# receiver_ra02.net
KiCad netlist of a schematic drawn in EAGLE
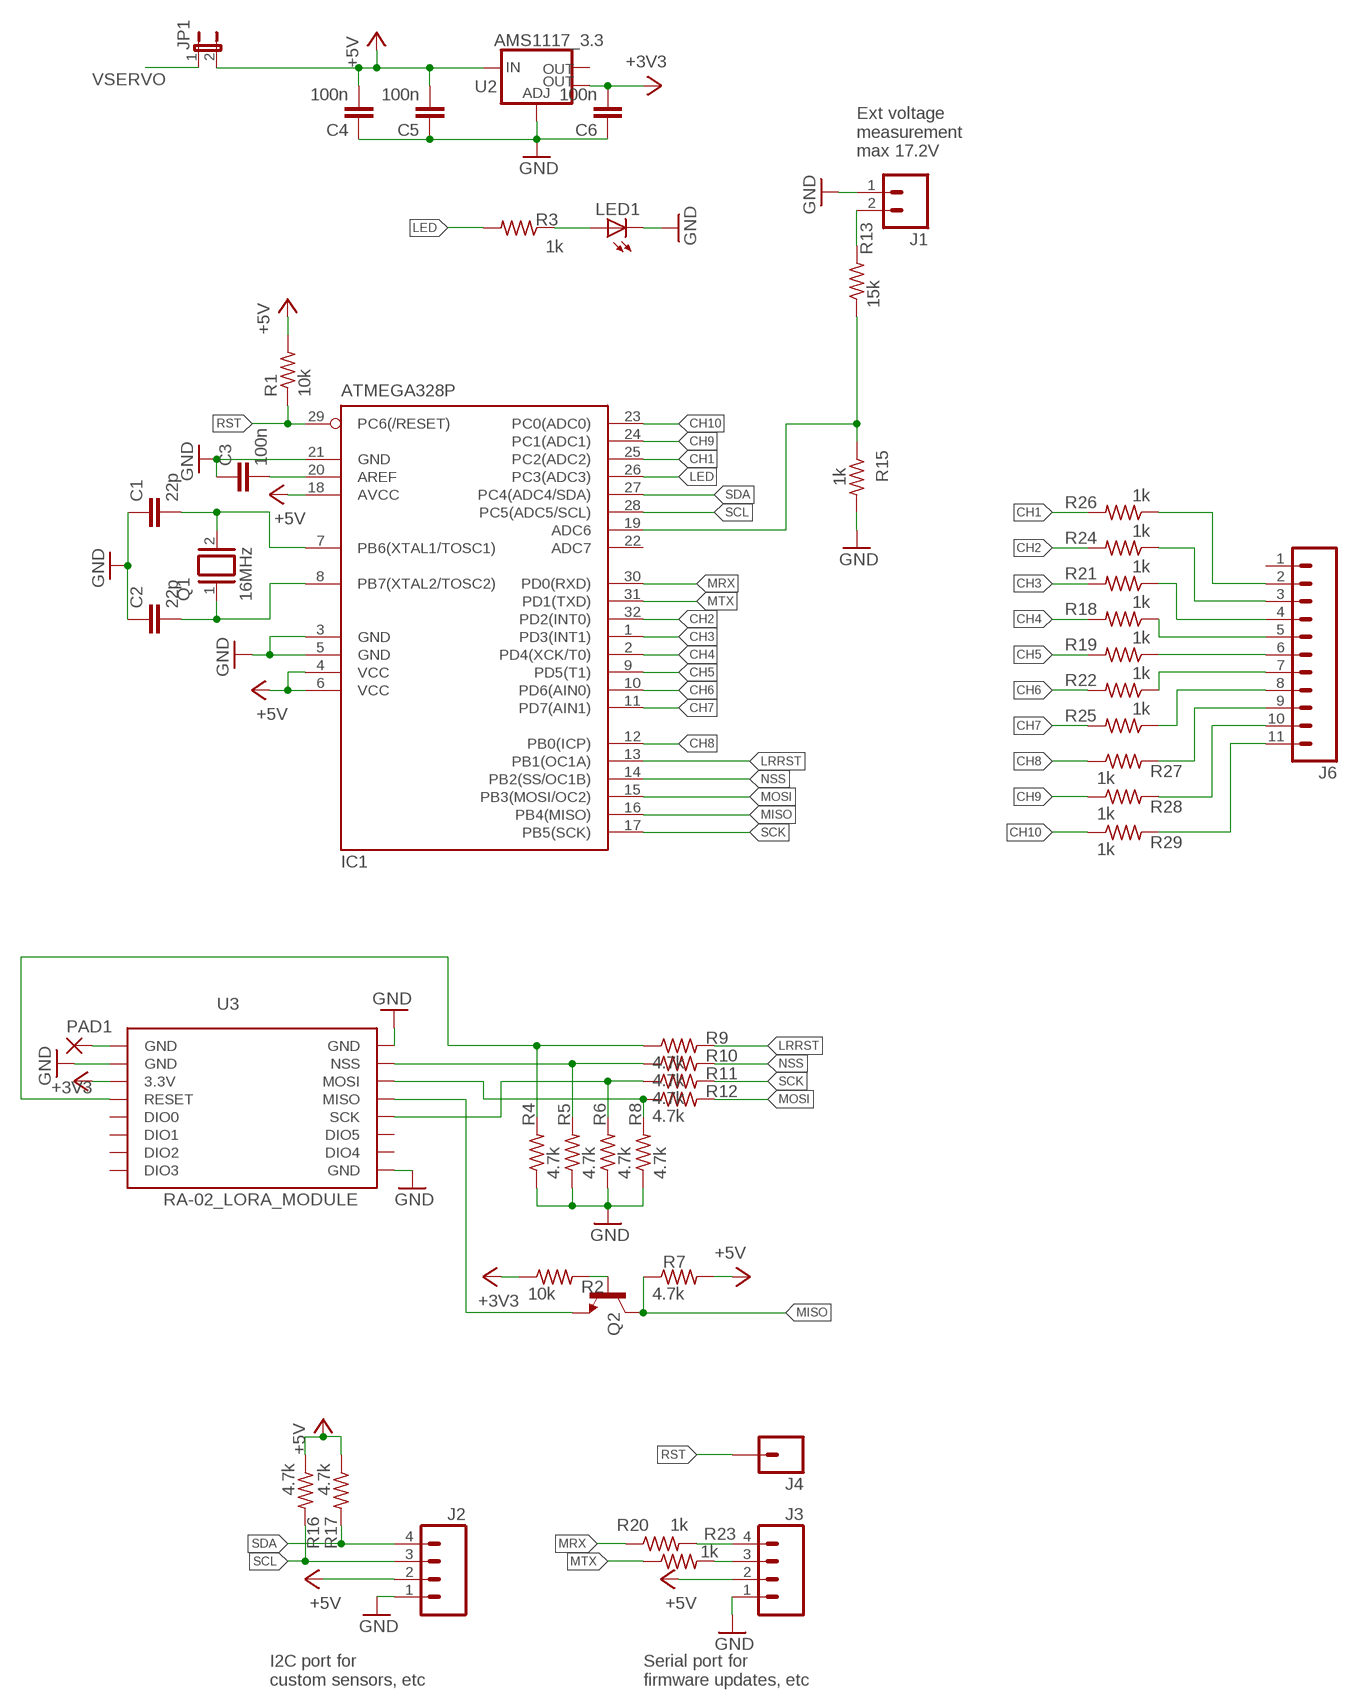
[diagram p0: schematic, sheet 1]

(export (version "E")
  (design (tool "Eeschema 10.0.6"))
  (components
    (comp (ref "C1")
      (value "22p")
      (footprint "eagle-import:C0805K")
      (libsource (lib "eagle-import") (part "C-EUC0805K"))
    )
    (comp (ref "C2")
      (value "22p")
      (footprint "eagle-import:C0805K")
      (libsource (lib "eagle-import") (part "C-EUC0805K"))
    )
    (comp (ref "C3")
      (value "100n")
      (footprint "eagle-import:C0805K")
      (libsource (lib "eagle-import") (part "C-EUC0805K"))
    )
    (comp (ref "C4")
      (value "100n")
      (footprint "eagle-import:C0805K")
      (libsource (lib "eagle-import") (part "C-EUC0805K"))
    )
    (comp (ref "C5")
      (value "100n")
      (footprint "eagle-import:C0805K")
      (libsource (lib "eagle-import") (part "C-EUC0805K"))
    )
    (comp (ref "C6")
      (value "100n")
      (footprint "eagle-import:C0805K")
      (libsource (lib "eagle-import") (part "C-EUC0805K"))
    )
    (comp (ref "IC1")
      (value "ATMEGA328P")
      (footprint "eagle-import:TQFP32-08")
      (fields (field (name "MPN") "ATMEGA8-16AU"))
      (libsource (lib "eagle-import") (part "MEGA8-AI"))
    )
    (comp (ref "J1")
      (value "M02PTH")
      (footprint "eagle-import:1X02")
      (libsource (lib "eagle-import") (part "M02PTH"))
    )
    (comp (ref "J2")
      (value "M04PTH")
      (footprint "eagle-import:1X04")
      (libsource (lib "eagle-import") (part "M04PTH"))
    )
    (comp (ref "J3")
      (value "M04PTH")
      (footprint "eagle-import:1X04")
      (libsource (lib "eagle-import") (part "M04PTH"))
    )
    (comp (ref "J4")
      (value "M01PTH")
      (footprint "eagle-import:1X01")
      (libsource (lib "eagle-import") (part "M01PTH"))
    )
    (comp (ref "J6")
      (value "M11PTH")
      (footprint "eagle-import:1X11")
      (libsource (lib "eagle-import") (part "M11PTH"))
    )
    (comp (ref "JP1")
      (value "JP1E")
      (footprint "eagle-import:JP1")
      (libsource (lib "eagle-import") (part "JP1E"))
    )
    (comp (ref "LED1")
      (value "LEDCHIPLED_1206")
      (footprint "eagle-import:CHIPLED_1206")
      (libsource (lib "eagle-import") (part "LEDCHIPLED_1206"))
    )
    (comp (ref "PAD1")
      (value "2,15/1,0")
      (footprint "eagle-import:2,15_1,0")
      (libsource (lib "eagle-import") (part "2,15/1,0"))
    )
    (comp (ref "Q1")
      (value "16MHz")
      (footprint "eagle-import:QS")
      (libsource (lib "eagle-import") (part "XTAL/S"))
    )
    (comp (ref "Q2")
      (value "BC817-16SMD")
      (footprint "eagle-import:SOT23-BEC")
      (libsource (lib "eagle-import") (part "BC817SMD-16"))
    )
    (comp (ref "R1")
      (value "10k")
      (footprint "eagle-import:R0805")
      (libsource (lib "eagle-import") (part "R-US_R0805"))
    )
    (comp (ref "R2")
      (value "10k")
      (footprint "eagle-import:R0805")
      (libsource (lib "eagle-import") (part "R-US_R0805"))
    )
    (comp (ref "R3")
      (value "1k")
      (footprint "eagle-import:R0805")
      (libsource (lib "eagle-import") (part "R-US_R0805"))
    )
    (comp (ref "R4")
      (value "4.7k")
      (footprint "eagle-import:R0805")
      (libsource (lib "eagle-import") (part "R-US_R0805"))
    )
    (comp (ref "R5")
      (value "4.7k")
      (footprint "eagle-import:R0805")
      (libsource (lib "eagle-import") (part "R-US_R0805"))
    )
    (comp (ref "R6")
      (value "4.7k")
      (footprint "eagle-import:R0805")
      (libsource (lib "eagle-import") (part "R-US_R0805"))
    )
    (comp (ref "R7")
      (value "4.7k")
      (footprint "eagle-import:R0805")
      (libsource (lib "eagle-import") (part "R-US_R0805"))
    )
    (comp (ref "R8")
      (value "4.7k")
      (footprint "eagle-import:R0805")
      (libsource (lib "eagle-import") (part "R-US_R0805"))
    )
    (comp (ref "R9")
      (value "4.7k")
      (footprint "eagle-import:R0805")
      (libsource (lib "eagle-import") (part "R-US_R0805"))
    )
    (comp (ref "R10")
      (value "4.7k")
      (footprint "eagle-import:R0805")
      (libsource (lib "eagle-import") (part "R-US_R0805"))
    )
    (comp (ref "R11")
      (value "4.7k")
      (footprint "eagle-import:R0805")
      (libsource (lib "eagle-import") (part "R-US_R0805"))
    )
    (comp (ref "R12")
      (value "4.7k")
      (footprint "eagle-import:R0805")
      (libsource (lib "eagle-import") (part "R-US_R0805"))
    )
    (comp (ref "R13")
      (value "15k")
      (footprint "eagle-import:R0805")
      (libsource (lib "eagle-import") (part "R-US_R0805"))
    )
    (comp (ref "R15")
      (value "1k")
      (footprint "eagle-import:R0805")
      (libsource (lib "eagle-import") (part "R-US_R0805"))
    )
    (comp (ref "R16")
      (value "4.7k")
      (footprint "eagle-import:R0805")
      (libsource (lib "eagle-import") (part "R-US_R0805"))
    )
    (comp (ref "R17")
      (value "4.7k")
      (footprint "eagle-import:R0805")
      (libsource (lib "eagle-import") (part "R-US_R0805"))
    )
    (comp (ref "R18")
      (value "1k")
      (footprint "eagle-import:R0805")
      (libsource (lib "eagle-import") (part "R-US_R0805"))
    )
    (comp (ref "R19")
      (value "1k")
      (footprint "eagle-import:R0805")
      (libsource (lib "eagle-import") (part "R-US_R0805"))
    )
    (comp (ref "R20")
      (value "1k")
      (footprint "eagle-import:R0805")
      (libsource (lib "eagle-import") (part "R-US_R0805"))
    )
    (comp (ref "R21")
      (value "1k")
      (footprint "eagle-import:R0805")
      (libsource (lib "eagle-import") (part "R-US_R0805"))
    )
    (comp (ref "R22")
      (value "1k")
      (footprint "eagle-import:R0805")
      (libsource (lib "eagle-import") (part "R-US_R0805"))
    )
    (comp (ref "R23")
      (value "1k")
      (footprint "eagle-import:R0805")
      (libsource (lib "eagle-import") (part "R-US_R0805"))
    )
    (comp (ref "R24")
      (value "1k")
      (footprint "eagle-import:R0805")
      (libsource (lib "eagle-import") (part "R-US_R0805"))
    )
    (comp (ref "R25")
      (value "1k")
      (footprint "eagle-import:R0805")
      (libsource (lib "eagle-import") (part "R-US_R0805"))
    )
    (comp (ref "R26")
      (value "1k")
      (footprint "eagle-import:R0805")
      (libsource (lib "eagle-import") (part "R-US_R0805"))
    )
    (comp (ref "R27")
      (value "1k")
      (footprint "eagle-import:R0805")
      (libsource (lib "eagle-import") (part "R-US_R0805"))
    )
    (comp (ref "R28")
      (value "1k")
      (footprint "eagle-import:R0805")
      (libsource (lib "eagle-import") (part "R-US_R0805"))
    )
    (comp (ref "R29")
      (value "1k")
      (footprint "eagle-import:R0805")
      (libsource (lib "eagle-import") (part "R-US_R0805"))
    )
    (comp (ref "U2")
      (value "AMS1117_3.3")
      (footprint "eagle-import:SOT223")
      (libsource (lib "eagle-import") (part "V_REG_LM1117SOT223"))
    )
    (comp (ref "U3")
      (value "RA-02_LORA_MODULE")
      (footprint "eagle-import:RA-02")
      (libsource (lib "eagle-import") (part "RA-02_LORA_MODULE"))
    )
  )
  (nets
    (net (code "1") (name "+3V3") (class "Default")
      (node (ref "C6") (pin "2") (pinfunction "2_2") (pintype "passive"))
      (node (ref "R2") (pin "1") (pinfunction "1_1") (pintype "passive"))
      (node (ref "U2") (pin "4") (pinfunction "OUT_4") (pintype "output"))
      (node (ref "U3") (pin "3.3V") (pinfunction "3.3V_3.3V") (pintype "power_in"))
    )
    (net (code "2") (name "+5V") (class "Default")
      (node (ref "C4") (pin "2") (pinfunction "2_2") (pintype "passive"))
      (node (ref "C5") (pin "2") (pinfunction "2_2") (pintype "passive"))
      (node (ref "IC1") (pin "18") (pinfunction "AVCC_18") (pintype "power_in"))
      (node (ref "IC1") (pin "4") (pinfunction "VCC_4") (pintype "power_in"))
      (node (ref "IC1") (pin "6") (pinfunction "VCC_6") (pintype "power_in"))
      (node (ref "J2") (pin "2") (pinfunction "2_2") (pintype "passive"))
      (node (ref "J3") (pin "2") (pinfunction "2_2") (pintype "passive"))
      (node (ref "JP1") (pin "2") (pinfunction "2_2") (pintype "passive"))
      (node (ref "R1") (pin "2") (pinfunction "2_2") (pintype "passive"))
      (node (ref "R16") (pin "1") (pinfunction "1_1") (pintype "passive"))
      (node (ref "R17") (pin "1") (pinfunction "1_1") (pintype "passive"))
      (node (ref "R7") (pin "2") (pinfunction "2_2") (pintype "passive"))
      (node (ref "U2") (pin "3") (pinfunction "IN_3") (pintype "input"))
    )
    (net (code "3") (name "/VSERVO") (class "Default")
      (node (ref "JP1") (pin "1") (pinfunction "1_1") (pintype "passive"))
    )
    (net (code "4") (name "CH1") (class "Default")
      (node (ref "IC1") (pin "25") (pinfunction "PC2(ADC2)_25") (pintype "bidirectional"))
      (node (ref "R26") (pin "2") (pinfunction "2_2") (pintype "passive"))
    )
    (net (code "5") (name "CH2") (class "Default")
      (node (ref "IC1") (pin "32") (pinfunction "PD2(INT0)_32") (pintype "bidirectional"))
      (node (ref "R24") (pin "2") (pinfunction "2_2") (pintype "passive"))
    )
    (net (code "6") (name "CH3") (class "Default")
      (node (ref "IC1") (pin "1") (pinfunction "PD3(INT1)_1") (pintype "bidirectional"))
      (node (ref "R21") (pin "2") (pinfunction "2_2") (pintype "passive"))
    )
    (net (code "7") (name "CH4") (class "Default")
      (node (ref "IC1") (pin "2") (pinfunction "PD4(XCK/T0)_2") (pintype "bidirectional"))
      (node (ref "R18") (pin "2") (pinfunction "2_2") (pintype "passive"))
    )
    (net (code "8") (name "CH5") (class "Default")
      (node (ref "IC1") (pin "9") (pinfunction "PD5(T1)_9") (pintype "bidirectional"))
      (node (ref "R19") (pin "2") (pinfunction "2_2") (pintype "passive"))
    )
    (net (code "9") (name "CH6") (class "Default")
      (node (ref "IC1") (pin "10") (pinfunction "PD6(AIN0)_10") (pintype "bidirectional"))
      (node (ref "R22") (pin "2") (pinfunction "2_2") (pintype "passive"))
    )
    (net (code "10") (name "CH7") (class "Default")
      (node (ref "IC1") (pin "11") (pinfunction "PD7(AIN1)_11") (pintype "bidirectional"))
      (node (ref "R25") (pin "2") (pinfunction "2_2") (pintype "passive"))
    )
    (net (code "11") (name "CH8") (class "Default")
      (node (ref "IC1") (pin "12") (pinfunction "PB0(ICP)_12") (pintype "bidirectional"))
      (node (ref "R27") (pin "1") (pinfunction "1_1") (pintype "passive"))
    )
    (net (code "12") (name "CH9") (class "Default")
      (node (ref "IC1") (pin "24") (pinfunction "PC1(ADC1)_24") (pintype "bidirectional"))
      (node (ref "R28") (pin "1") (pinfunction "1_1") (pintype "passive"))
    )
    (net (code "13") (name "CH10") (class "Default")
      (node (ref "IC1") (pin "23") (pinfunction "PC0(ADC0)_23") (pintype "bidirectional"))
      (node (ref "R29") (pin "1") (pinfunction "1_1") (pintype "passive"))
    )
    (net (code "14") (name "GND") (class "Default")
      (node (ref "C1") (pin "1") (pinfunction "1_1") (pintype "passive"))
      (node (ref "C2") (pin "1") (pinfunction "1_1") (pintype "passive"))
      (node (ref "C3") (pin "1") (pinfunction "1_1") (pintype "passive"))
      (node (ref "C4") (pin "1") (pinfunction "1_1") (pintype "passive"))
      (node (ref "C5") (pin "1") (pinfunction "1_1") (pintype "passive"))
      (node (ref "C6") (pin "1") (pinfunction "1_1") (pintype "passive"))
      (node (ref "IC1") (pin "21") (pinfunction "GND_21") (pintype "power_in"))
      (node (ref "IC1") (pin "3") (pinfunction "GND_3") (pintype "power_in"))
      (node (ref "IC1") (pin "5") (pinfunction "GND_5") (pintype "power_in"))
      (node (ref "J1") (pin "1") (pinfunction "1_1") (pintype "passive"))
      (node (ref "J2") (pin "1") (pinfunction "1_1") (pintype "passive"))
      (node (ref "J3") (pin "1") (pinfunction "1_1") (pintype "passive"))
      (node (ref "LED1") (pin "C") (pinfunction "C_C") (pintype "passive"))
      (node (ref "R15") (pin "2") (pinfunction "2_2") (pintype "passive"))
      (node (ref "R4") (pin "1") (pinfunction "1_1") (pintype "passive"))
      (node (ref "R5") (pin "1") (pinfunction "1_1") (pintype "passive"))
      (node (ref "R6") (pin "1") (pinfunction "1_1") (pintype "passive"))
      (node (ref "R8") (pin "1") (pinfunction "1_1") (pintype "passive"))
      (node (ref "U2") (pin "1") (pinfunction "ADJ_1") (pintype "input"))
      (node (ref "U3") (pin "GND@2") (pinfunction "GND_GND@2") (pintype "power_in"))
      (node (ref "U3") (pin "GND@3") (pinfunction "GND_GND@3") (pintype "power_in"))
      (node (ref "U3") (pin "GND@4") (pinfunction "GND_GND@4") (pintype "power_in"))
    )
    (net (code "15") (name "LED") (class "Default")
      (node (ref "IC1") (pin "26") (pinfunction "PC3(ADC3)_26") (pintype "bidirectional"))
      (node (ref "R3") (pin "2") (pinfunction "2_2") (pintype "passive"))
    )
    (net (code "16") (name "LRRST") (class "Default")
      (node (ref "IC1") (pin "13") (pinfunction "PB1(OC1A)_13") (pintype "bidirectional"))
      (node (ref "R9") (pin "2") (pinfunction "2_2") (pintype "passive"))
    )
    (net (code "17") (name "MISO") (class "Default")
      (node (ref "IC1") (pin "16") (pinfunction "PB4(MISO)_16") (pintype "bidirectional"))
      (node (ref "Q2") (pin "C") (pinfunction "C_C") (pintype "passive"))
      (node (ref "R7") (pin "1") (pinfunction "1_1") (pintype "passive"))
    )
    (net (code "18") (name "MOSI") (class "Default")
      (node (ref "IC1") (pin "15") (pinfunction "PB3(MOSI/OC2)_15") (pintype "bidirectional"))
      (node (ref "R12") (pin "2") (pinfunction "2_2") (pintype "passive"))
    )
    (net (code "19") (name "MRX") (class "Default")
      (node (ref "IC1") (pin "30") (pinfunction "PD0(RXD)_30") (pintype "bidirectional"))
      (node (ref "R20") (pin "1") (pinfunction "1_1") (pintype "passive"))
    )
    (net (code "20") (name "MTX") (class "Default")
      (node (ref "IC1") (pin "31") (pinfunction "PD1(TXD)_31") (pintype "bidirectional"))
      (node (ref "R23") (pin "1") (pinfunction "1_1") (pintype "passive"))
    )
    (net (code "21") (name "NSS") (class "Default")
      (node (ref "IC1") (pin "14") (pinfunction "PB2(SS/OC1B)_14") (pintype "bidirectional"))
      (node (ref "R10") (pin "2") (pinfunction "2_2") (pintype "passive"))
    )
    (net (code "22") (name "Net-(IC1-ADC6)") (class "Default")
      (node (ref "IC1") (pin "19") (pinfunction "ADC6_19") (pintype "bidirectional"))
      (node (ref "R13") (pin "1") (pinfunction "1_1") (pintype "passive"))
      (node (ref "R15") (pin "1") (pinfunction "1_1") (pintype "passive"))
    )
    (net (code "23") (name "Net-(IC1-AREF)") (class "Default")
      (node (ref "C3") (pin "2") (pinfunction "2_2") (pintype "passive"))
      (node (ref "IC1") (pin "20") (pinfunction "AREF_20") (pintype "passive"))
    )
    (net (code "24") (name "Net-(IC1-PB6(XTAL1{slash}TOSC1))") (class "Default")
      (node (ref "C1") (pin "2") (pinfunction "2_2") (pintype "passive"))
      (node (ref "IC1") (pin "7") (pinfunction "PB6(XTAL1/TOSC1)_7") (pintype "bidirectional"))
      (node (ref "Q1") (pin "2") (pinfunction "2_2") (pintype "passive"))
    )
    (net (code "25") (name "Net-(IC1-PB7(XTAL2{slash}TOSC2))") (class "Default")
      (node (ref "C2") (pin "2") (pinfunction "2_2") (pintype "passive"))
      (node (ref "IC1") (pin "8") (pinfunction "PB7(XTAL2/TOSC2)_8") (pintype "bidirectional"))
      (node (ref "Q1") (pin "1") (pinfunction "1_1") (pintype "passive"))
    )
    (net (code "26") (name "Net-(J1-Pad2)") (class "Default")
      (node (ref "J1") (pin "2") (pinfunction "2_2") (pintype "passive"))
      (node (ref "R13") (pin "2") (pinfunction "2_2") (pintype "passive"))
    )
    (net (code "27") (name "Net-(J3-Pad3)") (class "Default")
      (node (ref "J3") (pin "3") (pinfunction "3_3") (pintype "passive"))
      (node (ref "R23") (pin "2") (pinfunction "2_2") (pintype "passive"))
    )
    (net (code "28") (name "Net-(J3-Pad4)") (class "Default")
      (node (ref "J3") (pin "4") (pinfunction "4_4") (pintype "passive"))
      (node (ref "R20") (pin "2") (pinfunction "2_2") (pintype "passive"))
    )
    (net (code "29") (name "Net-(J6-Pad2)") (class "Default")
      (node (ref "J6") (pin "2") (pinfunction "2_2") (pintype "passive"))
      (node (ref "R26") (pin "1") (pinfunction "1_1") (pintype "passive"))
    )
    (net (code "30") (name "Net-(J6-Pad3)") (class "Default")
      (node (ref "J6") (pin "3") (pinfunction "3_3") (pintype "passive"))
      (node (ref "R24") (pin "1") (pinfunction "1_1") (pintype "passive"))
    )
    (net (code "31") (name "Net-(J6-Pad4)") (class "Default")
      (node (ref "J6") (pin "4") (pinfunction "4_4") (pintype "passive"))
      (node (ref "R21") (pin "1") (pinfunction "1_1") (pintype "passive"))
    )
    (net (code "32") (name "Net-(J6-Pad5)") (class "Default")
      (node (ref "J6") (pin "5") (pinfunction "5_5") (pintype "passive"))
      (node (ref "R18") (pin "1") (pinfunction "1_1") (pintype "passive"))
    )
    (net (code "33") (name "Net-(J6-Pad6)") (class "Default")
      (node (ref "J6") (pin "6") (pinfunction "6_6") (pintype "passive"))
      (node (ref "R19") (pin "1") (pinfunction "1_1") (pintype "passive"))
    )
    (net (code "34") (name "Net-(J6-Pad7)") (class "Default")
      (node (ref "J6") (pin "7") (pinfunction "7_7") (pintype "passive"))
      (node (ref "R22") (pin "1") (pinfunction "1_1") (pintype "passive"))
    )
    (net (code "35") (name "Net-(J6-Pad8)") (class "Default")
      (node (ref "J6") (pin "8") (pinfunction "8_8") (pintype "passive"))
      (node (ref "R25") (pin "1") (pinfunction "1_1") (pintype "passive"))
    )
    (net (code "36") (name "Net-(J6-Pad9)") (class "Default")
      (node (ref "J6") (pin "9") (pinfunction "9_9") (pintype "passive"))
      (node (ref "R27") (pin "2") (pinfunction "2_2") (pintype "passive"))
    )
    (net (code "37") (name "Net-(J6-Pad10)") (class "Default")
      (node (ref "J6") (pin "10") (pinfunction "10_10") (pintype "passive"))
      (node (ref "R28") (pin "2") (pinfunction "2_2") (pintype "passive"))
    )
    (net (code "38") (name "Net-(J6-Pad11)") (class "Default")
      (node (ref "J6") (pin "11") (pinfunction "11_11") (pintype "passive"))
      (node (ref "R29") (pin "2") (pinfunction "2_2") (pintype "passive"))
    )
    (net (code "39") (name "Net-(LED1-PadA)") (class "Default")
      (node (ref "LED1") (pin "A") (pinfunction "A_A") (pintype "passive"))
      (node (ref "R3") (pin "1") (pinfunction "1_1") (pintype "passive"))
    )
    (net (code "40") (name "Net-(PAD1-P)") (class "Default")
      (node (ref "PAD1") (pin "1") (pinfunction "P_1") (pintype "passive"))
      (node (ref "U3") (pin "GND") (pinfunction "GND_GND") (pintype "power_in"))
    )
    (net (code "41") (name "Net-(Q2-PadB)") (class "Default")
      (node (ref "Q2") (pin "B") (pinfunction "B_B") (pintype "passive"))
      (node (ref "R2") (pin "2") (pinfunction "2_2") (pintype "passive"))
    )
    (net (code "42") (name "Net-(Q2-PadE)") (class "Default")
      (node (ref "Q2") (pin "E") (pinfunction "E_E") (pintype "passive"))
      (node (ref "U3") (pin "MISO") (pinfunction "MISO_MISO") (pintype "bidirectional"))
    )
    (net (code "43") (name "Net-(R4-Pad2)") (class "Default")
      (node (ref "R4") (pin "2") (pinfunction "2_2") (pintype "passive"))
      (node (ref "R9") (pin "1") (pinfunction "1_1") (pintype "passive"))
      (node (ref "U3") (pin "RESET") (pinfunction "RESET_RESET") (pintype "bidirectional"))
    )
    (net (code "44") (name "Net-(R10-Pad1)") (class "Default")
      (node (ref "R10") (pin "1") (pinfunction "1_1") (pintype "passive"))
      (node (ref "R5") (pin "2") (pinfunction "2_2") (pintype "passive"))
      (node (ref "U3") (pin "NSS") (pinfunction "NSS_NSS") (pintype "bidirectional"))
    )
    (net (code "45") (name "Net-(R11-Pad1)") (class "Default")
      (node (ref "R11") (pin "1") (pinfunction "1_1") (pintype "passive"))
      (node (ref "R6") (pin "2") (pinfunction "2_2") (pintype "passive"))
      (node (ref "U3") (pin "SCK") (pinfunction "SCK_SCK") (pintype "bidirectional"))
    )
    (net (code "46") (name "Net-(R12-Pad1)") (class "Default")
      (node (ref "R12") (pin "1") (pinfunction "1_1") (pintype "passive"))
      (node (ref "R8") (pin "2") (pinfunction "2_2") (pintype "passive"))
      (node (ref "U3") (pin "MOSI") (pinfunction "MOSI_MOSI") (pintype "bidirectional"))
    )
    (net (code "47") (name "RST") (class "Default")
      (node (ref "IC1") (pin "29") (pinfunction "PC6(/RESET)_29") (pintype "bidirectional"))
      (node (ref "J4") (pin "1") (pinfunction "1_1") (pintype "passive"))
      (node (ref "R1") (pin "1") (pinfunction "1_1") (pintype "passive"))
    )
    (net (code "48") (name "SCK") (class "Default")
      (node (ref "IC1") (pin "17") (pinfunction "PB5(SCK)_17") (pintype "bidirectional"))
      (node (ref "R11") (pin "2") (pinfunction "2_2") (pintype "passive"))
    )
    (net (code "49") (name "SCL") (class "Default")
      (node (ref "IC1") (pin "28") (pinfunction "PC5(ADC5/SCL)_28") (pintype "bidirectional"))
      (node (ref "J2") (pin "3") (pinfunction "3_3") (pintype "passive"))
      (node (ref "R16") (pin "2") (pinfunction "2_2") (pintype "passive"))
    )
    (net (code "50") (name "SDA") (class "Default")
      (node (ref "IC1") (pin "27") (pinfunction "PC4(ADC4/SDA)_27") (pintype "bidirectional"))
      (node (ref "J2") (pin "4") (pinfunction "4_4") (pintype "passive"))
      (node (ref "R17") (pin "2") (pinfunction "2_2") (pintype "passive"))
    )
    (net (code "51") (name "unconnected-(IC1-ADC7-Pad22)") (class "Default")
      (node (ref "IC1") (pin "22") (pinfunction "ADC7_22") (pintype "bidirectional"))
    )
    (net (code "52") (name "unconnected-(J6-Pad1)") (class "Default")
      (node (ref "J6") (pin "1") (pinfunction "1_1") (pintype "passive"))
    )
    (net (code "53") (name "unconnected-(U2-OUT-Pad2)") (class "Default")
      (node (ref "U2") (pin "2") (pinfunction "OUT_2") (pintype "output"))
    )
    (net (code "54") (name "unconnected-(U3-PadDIO0)") (class "Default")
      (node (ref "U3") (pin "DIO0") (pinfunction "DIO0_DIO0") (pintype "bidirectional"))
    )
    (net (code "55") (name "unconnected-(U3-PadDIO1)") (class "Default")
      (node (ref "U3") (pin "DIO1") (pinfunction "DIO1_DIO1") (pintype "bidirectional"))
    )
    (net (code "56") (name "unconnected-(U3-PadDIO2)") (class "Default")
      (node (ref "U3") (pin "DIO2") (pinfunction "DIO2_DIO2") (pintype "bidirectional"))
    )
    (net (code "57") (name "unconnected-(U3-PadDIO3)") (class "Default")
      (node (ref "U3") (pin "DIO3") (pinfunction "DIO3_DIO3") (pintype "bidirectional"))
    )
    (net (code "58") (name "unconnected-(U3-PadDIO4)") (class "Default")
      (node (ref "U3") (pin "DIO4") (pinfunction "DIO4_DIO4") (pintype "bidirectional"))
    )
    (net (code "59") (name "unconnected-(U3-PadDIO5)") (class "Default")
      (node (ref "U3") (pin "DIO5") (pinfunction "DIO5_DIO5") (pintype "bidirectional"))
    )
  )
)
